# lightclock_0.net
KiCad netlist of a schematic drawn in EAGLE
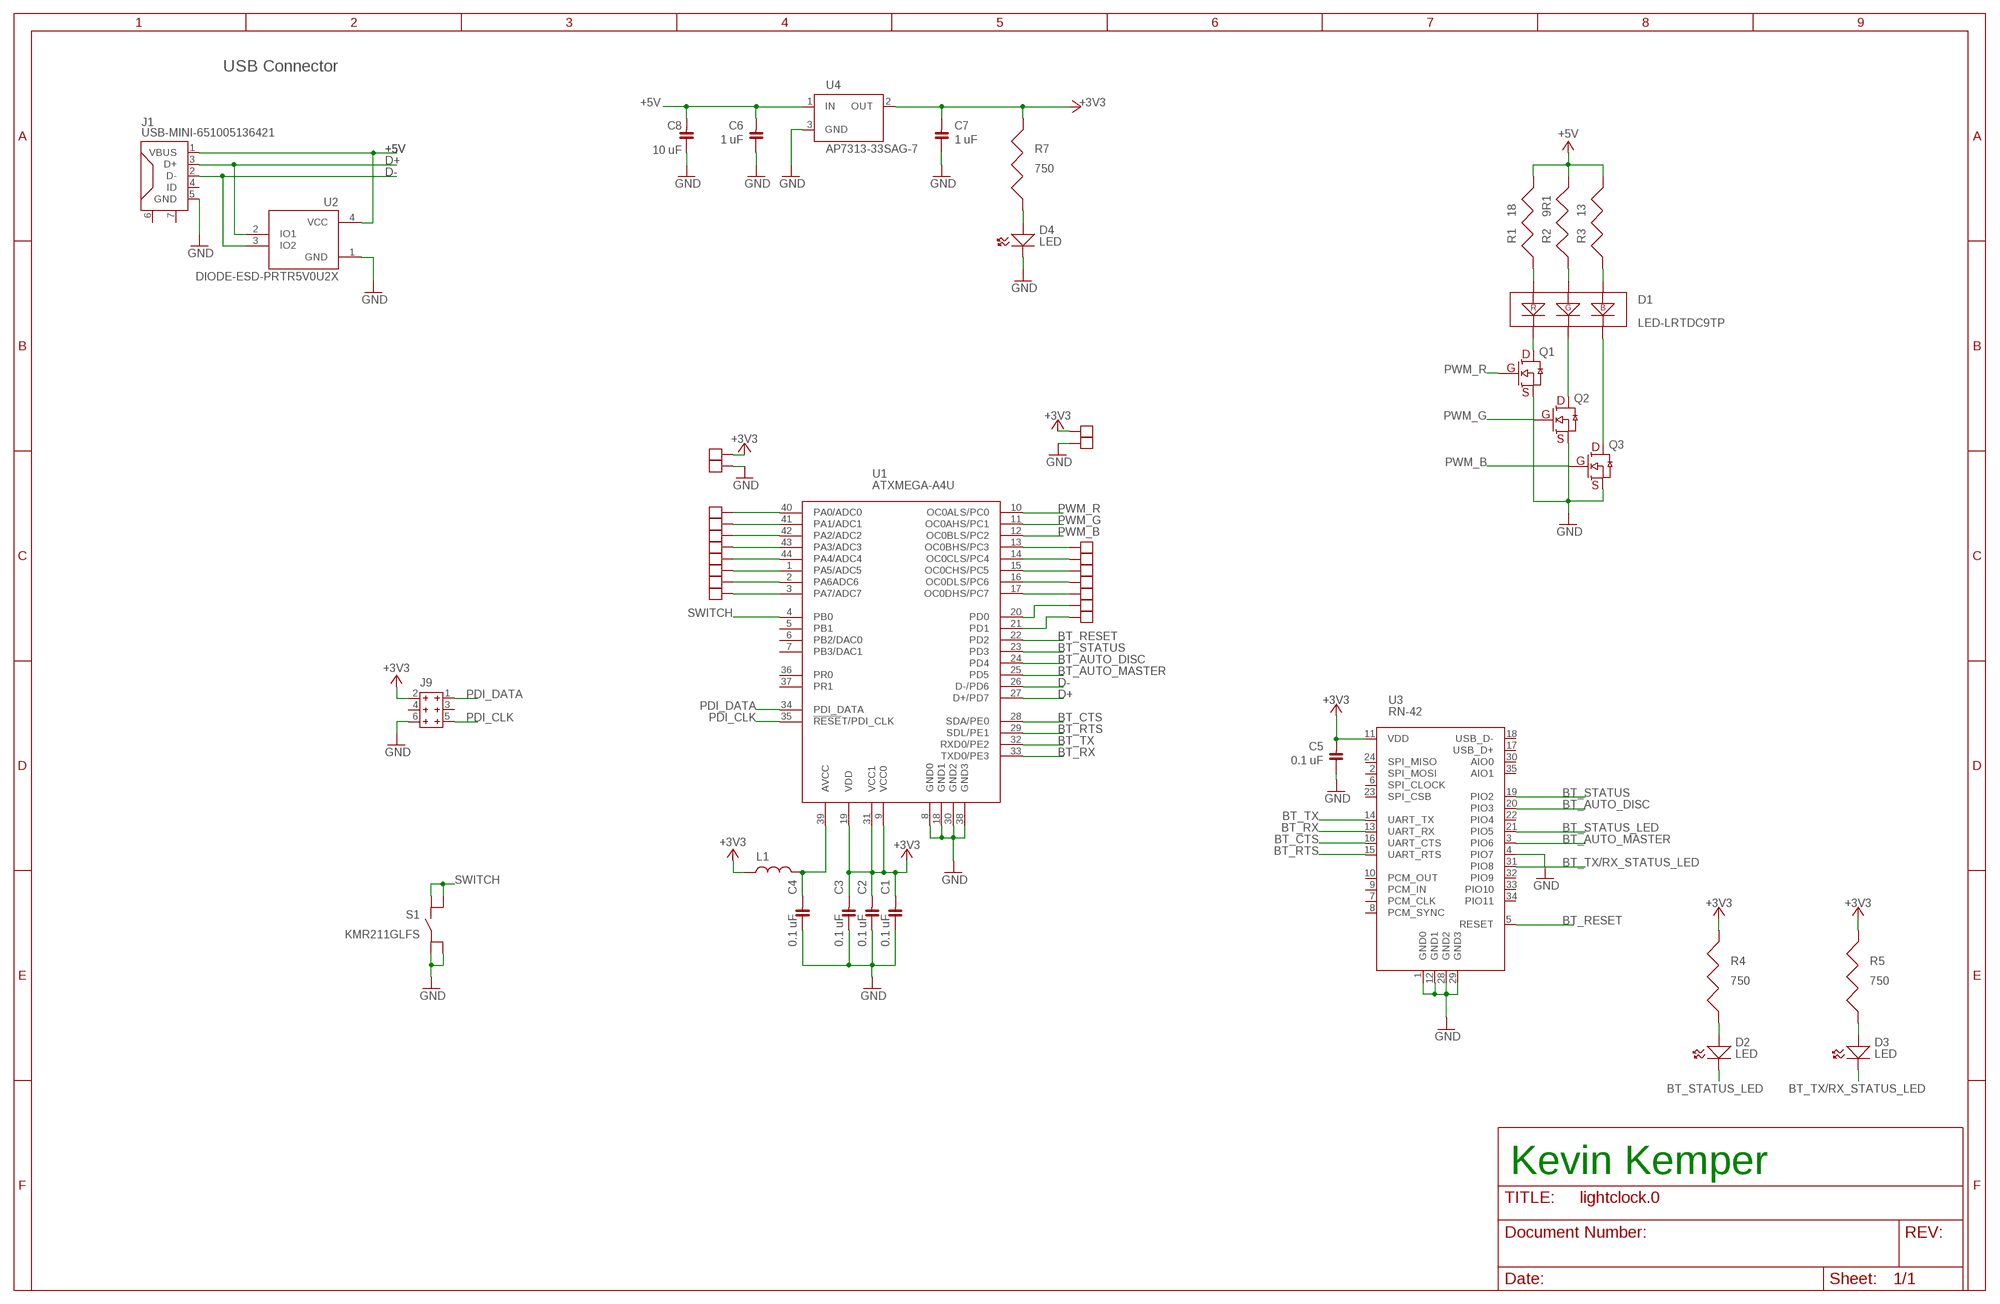
[diagram p0: schematic, sheet 1]

(export (version "E")
  (design (tool "Eeschema 10.0.6"))
  (components
    (comp (ref "C1")
      (value "0.1 uF")
      (footprint "eagle-import:0603")
      (libsource (lib "eagle-import") (part "CAP-0603"))
    )
    (comp (ref "C2")
      (value "0.1 uF")
      (footprint "eagle-import:0603")
      (libsource (lib "eagle-import") (part "CAP-0603"))
    )
    (comp (ref "C3")
      (value "0.1 uF")
      (footprint "eagle-import:0603")
      (libsource (lib "eagle-import") (part "CAP-0603"))
    )
    (comp (ref "C4")
      (value "0.1 uF")
      (footprint "eagle-import:0603")
      (libsource (lib "eagle-import") (part "CAP-0603"))
    )
    (comp (ref "C5")
      (value "0.1 uF")
      (footprint "eagle-import:0603")
      (libsource (lib "eagle-import") (part "CAP-0603"))
    )
    (comp (ref "C6")
      (value "1 uF")
      (footprint "eagle-import:0603")
      (libsource (lib "eagle-import") (part "CAP-0603"))
    )
    (comp (ref "C7")
      (value "1 uF")
      (footprint "eagle-import:0603")
      (libsource (lib "eagle-import") (part "CAP-0603"))
    )
    (comp (ref "C8")
      (value "10 uF")
      (footprint "eagle-import:0805")
      (libsource (lib "eagle-import") (part "CAP-0805"))
    )
    (comp (ref "D1")
      (value "LED-LRTDC9TP")
      (footprint "eagle-import:LRTDC9TP-EAFB-GHQN")
      (libsource (lib "eagle-import") (part "LED-LRTDC9TP"))
    )
    (comp (ref "D2")
      (value "LED")
      (footprint "eagle-import:0603-POL")
      (libsource (lib "eagle-import") (part "LED"))
    )
    (comp (ref "D3")
      (value "LED")
      (footprint "eagle-import:0603-POL")
      (libsource (lib "eagle-import") (part "LED"))
    )
    (comp (ref "D4")
      (value "LED")
      (footprint "eagle-import:0603-POL")
      (libsource (lib "eagle-import") (part "LED"))
    )
    (comp (ref "J1")
      (value "USB-MINI-651005136421")
      (footprint "eagle-import:651005136421")
      (libsource (lib "eagle-import") (part "USB-MINI-651005136421"))
    )
    (comp (ref "J2")
      (value "TESTPAD")
      (footprint "eagle-import:HEADER-1X1")
      (libsource (lib "eagle-import") (part "TESTPAD"))
    )
    (comp (ref "J3")
      (value "TESTPAD")
      (footprint "eagle-import:HEADER-1X1")
      (libsource (lib "eagle-import") (part "TESTPAD"))
    )
    (comp (ref "J4")
      (value "TESTPAD")
      (footprint "eagle-import:HEADER-1X1")
      (libsource (lib "eagle-import") (part "TESTPAD"))
    )
    (comp (ref "J5")
      (value "TESTPAD")
      (footprint "eagle-import:HEADER-1X1")
      (libsource (lib "eagle-import") (part "TESTPAD"))
    )
    (comp (ref "J6")
      (value "TESTPAD")
      (footprint "eagle-import:HEADER-1X1")
      (libsource (lib "eagle-import") (part "TESTPAD"))
    )
    (comp (ref "J7")
      (value "TESTPAD")
      (footprint "eagle-import:HEADER-1X1")
      (libsource (lib "eagle-import") (part "TESTPAD"))
    )
    (comp (ref "J8")
      (value "TESTPAD")
      (footprint "eagle-import:HEADER-1X1")
      (libsource (lib "eagle-import") (part "TESTPAD"))
    )
    (comp (ref "J9")
      (value "HEADER-2X6")
      (footprint "eagle-import:HEADER-2X6")
      (libsource (lib "eagle-import") (part "HEADER-2X6"))
    )
    (comp (ref "J10")
      (value "TESTPAD")
      (footprint "eagle-import:HEADER-1X1")
      (libsource (lib "eagle-import") (part "TESTPAD"))
    )
    (comp (ref "J11")
      (value "TESTPAD")
      (footprint "eagle-import:HEADER-1X1")
      (libsource (lib "eagle-import") (part "TESTPAD"))
    )
    (comp (ref "J12")
      (value "TESTPAD")
      (footprint "eagle-import:HEADER-1X1")
      (libsource (lib "eagle-import") (part "TESTPAD"))
    )
    (comp (ref "J13")
      (value "TESTPAD")
      (footprint "eagle-import:HEADER-1X1")
      (libsource (lib "eagle-import") (part "TESTPAD"))
    )
    (comp (ref "J14")
      (value "TESTPAD")
      (footprint "eagle-import:HEADER-1X1")
      (libsource (lib "eagle-import") (part "TESTPAD"))
    )
    (comp (ref "J15")
      (value "TESTPAD")
      (footprint "eagle-import:HEADER-1X1")
      (libsource (lib "eagle-import") (part "TESTPAD"))
    )
    (comp (ref "J16")
      (value "TESTPAD")
      (footprint "eagle-import:HEADER-1X1")
      (libsource (lib "eagle-import") (part "TESTPAD"))
    )
    (comp (ref "J17")
      (value "TESTPAD")
      (footprint "eagle-import:HEADER-1X1")
      (libsource (lib "eagle-import") (part "TESTPAD"))
    )
    (comp (ref "J18")
      (value "TESTPAD")
      (footprint "eagle-import:HEADER-1X1")
      (libsource (lib "eagle-import") (part "TESTPAD"))
    )
    (comp (ref "J19")
      (value "TESTPAD")
      (footprint "eagle-import:HEADER-1X1")
      (libsource (lib "eagle-import") (part "TESTPAD"))
    )
    (comp (ref "J20")
      (value "TESTPAD")
      (footprint "eagle-import:HEADER-1X1")
      (libsource (lib "eagle-import") (part "TESTPAD"))
    )
    (comp (ref "J21")
      (value "TESTPAD")
      (footprint "eagle-import:HEADER-1X1")
      (libsource (lib "eagle-import") (part "TESTPAD"))
    )
    (comp (ref "L1")
      (value "IND-0603")
      (footprint "eagle-import:0603")
      (libsource (lib "eagle-import") (part "IND-0603"))
    )
    (comp (ref "Q1")
      (value "BSS138")
      (footprint "eagle-import:SOT-23")
      (libsource (lib "eagle-import") (part "BSS138"))
    )
    (comp (ref "Q2")
      (value "BSS138")
      (footprint "eagle-import:SOT-23")
      (libsource (lib "eagle-import") (part "BSS138"))
    )
    (comp (ref "Q3")
      (value "BSS138")
      (footprint "eagle-import:SOT-23")
      (libsource (lib "eagle-import") (part "BSS138"))
    )
    (comp (ref "R1")
      (value "18")
      (footprint "eagle-import:2010")
      (libsource (lib "eagle-import") (part "RES2010"))
    )
    (comp (ref "R2")
      (value "9R1")
      (footprint "eagle-import:2010")
      (libsource (lib "eagle-import") (part "RES2010"))
    )
    (comp (ref "R3")
      (value "13")
      (footprint "eagle-import:2010")
      (libsource (lib "eagle-import") (part "RES2010"))
    )
    (comp (ref "R4")
      (value "750")
      (footprint "eagle-import:0603")
      (libsource (lib "eagle-import") (part "RES-0603"))
    )
    (comp (ref "R5")
      (value "750")
      (footprint "eagle-import:0603")
      (libsource (lib "eagle-import") (part "RES-0603"))
    )
    (comp (ref "R7")
      (value "750")
      (footprint "eagle-import:0603")
      (libsource (lib "eagle-import") (part "RES-0603"))
    )
    (comp (ref "S1")
      (value "KMR211GLFS")
      (footprint "eagle-import:KMR211GLFS")
      (libsource (lib "eagle-import") (part "KMR211GLFS"))
    )
    (comp (ref "U1")
      (value "ATXMEGA-A4U")
      (footprint "eagle-import:ATXMEGA16A4U-AUR")
      (libsource (lib "eagle-import") (part "ATXMEGA-A4U"))
    )
    (comp (ref "U2")
      (value "DIODE-ESD-PRTR5V0U2X")
      (footprint "eagle-import:PRTR5V0U2X")
      (libsource (lib "eagle-import") (part "DIODE-ESD-PRTR5V0U2X"))
    )
    (comp (ref "U3")
      (value "RN-42")
      (footprint "eagle-import:RN-42")
      (libsource (lib "eagle-import") (part "RN-42"))
    )
    (comp (ref "U4")
      (value "AP7313-33SAG-7")
      (footprint "eagle-import:AP7313-33SAG-7")
      (libsource (lib "eagle-import") (part "AP7313-33SAG-7"))
    )
  )
  (nets
    (net (code "1") (name "+3V3") (class "Default")
      (node (ref "C1") (pin "1") (pinfunction "1_1") (pintype "bidirectional"))
      (node (ref "C2") (pin "1") (pinfunction "1_1") (pintype "bidirectional"))
      (node (ref "C3") (pin "1") (pinfunction "1_1") (pintype "bidirectional"))
      (node (ref "C5") (pin "1") (pinfunction "1_1") (pintype "bidirectional"))
      (node (ref "C7") (pin "1") (pinfunction "1_1") (pintype "bidirectional"))
      (node (ref "J18") (pin "1") (pinfunction "P$1_1") (pintype "bidirectional"))
      (node (ref "J20") (pin "1") (pinfunction "P$1_1") (pintype "bidirectional"))
      (node (ref "J9") (pin "2") (pinfunction "2_2") (pintype "bidirectional"))
      (node (ref "L1") (pin "1") (pinfunction "P$1_1") (pintype "bidirectional"))
      (node (ref "R4") (pin "2") (pinfunction "P$2_2") (pintype "bidirectional"))
      (node (ref "R5") (pin "2") (pinfunction "P$2_2") (pintype "bidirectional"))
      (node (ref "R7") (pin "2") (pinfunction "P$2_2") (pintype "bidirectional"))
      (node (ref "U1") (pin "19") (pinfunction "VDD_19") (pintype "bidirectional"))
      (node (ref "U1") (pin "31") (pinfunction "VCC1_31") (pintype "bidirectional"))
      (node (ref "U1") (pin "9") (pinfunction "VCC0_9") (pintype "bidirectional"))
      (node (ref "U3") (pin "11") (pinfunction "VDD_11") (pintype "bidirectional"))
      (node (ref "U4") (pin "2") (pinfunction "OUT_2") (pintype "bidirectional"))
    )
    (net (code "2") (name "+5V") (class "Default")
      (node (ref "C6") (pin "1") (pinfunction "1_1") (pintype "bidirectional"))
      (node (ref "C8") (pin "1") (pinfunction "1_1") (pintype "bidirectional"))
      (node (ref "J1") (pin "1") (pinfunction "VBUS_1") (pintype "bidirectional"))
      (node (ref "R1") (pin "2") (pinfunction "P$2_2") (pintype "bidirectional"))
      (node (ref "R2") (pin "2") (pinfunction "P$2_2") (pintype "bidirectional"))
      (node (ref "R3") (pin "2") (pinfunction "P$2_2") (pintype "bidirectional"))
      (node (ref "U2") (pin "4") (pinfunction "VCC_4") (pintype "bidirectional"))
      (node (ref "U4") (pin "1") (pinfunction "IN_1") (pintype "bidirectional"))
    )
    (net (code "3") (name "/BT_AUTO_DISC") (class "Default")
      (node (ref "U1") (pin "24") (pinfunction "PD4_24") (pintype "bidirectional"))
      (node (ref "U3") (pin "20") (pinfunction "PIO3_20") (pintype "bidirectional"))
    )
    (net (code "4") (name "/BT_AUTO_MASTER") (class "Default")
      (node (ref "U1") (pin "25") (pinfunction "PD5_25") (pintype "bidirectional"))
      (node (ref "U3") (pin "3") (pinfunction "PIO6_3") (pintype "bidirectional"))
    )
    (net (code "5") (name "/BT_CTS") (class "Default")
      (node (ref "U1") (pin "28") (pinfunction "SDA/PE0_28") (pintype "bidirectional"))
      (node (ref "U3") (pin "16") (pinfunction "UART_CTS_16") (pintype "bidirectional"))
    )
    (net (code "6") (name "/BT_RESET") (class "Default")
      (node (ref "U1") (pin "22") (pinfunction "PD2_22") (pintype "bidirectional"))
      (node (ref "U3") (pin "5") (pinfunction "RESET_5") (pintype "bidirectional"))
    )
    (net (code "7") (name "/BT_RTS") (class "Default")
      (node (ref "U1") (pin "29") (pinfunction "SDL/PE1_29") (pintype "bidirectional"))
      (node (ref "U3") (pin "15") (pinfunction "UART_RTS_15") (pintype "bidirectional"))
    )
    (net (code "8") (name "/BT_RX") (class "Default")
      (node (ref "U1") (pin "33") (pinfunction "TXD0/PE3_33") (pintype "bidirectional"))
      (node (ref "U3") (pin "13") (pinfunction "UART_RX_13") (pintype "bidirectional"))
    )
    (net (code "9") (name "/BT_STATUS") (class "Default")
      (node (ref "U1") (pin "23") (pinfunction "PD3_23") (pintype "bidirectional"))
      (node (ref "U3") (pin "19") (pinfunction "PIO2_19") (pintype "bidirectional"))
    )
    (net (code "10") (name "/BT_STATUS_LED") (class "Default")
      (node (ref "D2") (pin "2") (pinfunction "2_2") (pintype "bidirectional"))
      (node (ref "U3") (pin "21") (pinfunction "PIO5_21") (pintype "bidirectional"))
    )
    (net (code "11") (name "/BT_TX") (class "Default")
      (node (ref "U1") (pin "32") (pinfunction "RXD0/PE2_32") (pintype "bidirectional"))
      (node (ref "U3") (pin "14") (pinfunction "UART_TX_14") (pintype "bidirectional"))
    )
    (net (code "12") (name "/BT_TX{slash}RX_STATUS_LED") (class "Default")
      (node (ref "D3") (pin "2") (pinfunction "2_2") (pintype "bidirectional"))
      (node (ref "U3") (pin "31") (pinfunction "PIO8_31") (pintype "bidirectional"))
    )
    (net (code "13") (name "/D+") (class "Default")
      (node (ref "J1") (pin "3") (pinfunction "D+_3") (pintype "bidirectional"))
      (node (ref "U1") (pin "27") (pinfunction "D+/PD7_27") (pintype "bidirectional"))
      (node (ref "U2") (pin "2") (pinfunction "IO1_2") (pintype "bidirectional"))
    )
    (net (code "14") (name "/D-") (class "Default")
      (node (ref "J1") (pin "2") (pinfunction "D-_2") (pintype "bidirectional"))
      (node (ref "U1") (pin "26") (pinfunction "D-/PD6_26") (pintype "bidirectional"))
      (node (ref "U2") (pin "3") (pinfunction "IO2_3") (pintype "bidirectional"))
    )
    (net (code "15") (name "/PDI_CLK") (class "Default")
      (node (ref "J9") (pin "5") (pinfunction "5_5") (pintype "bidirectional"))
      (node (ref "U1") (pin "35") (pinfunction "~{RESE}T/PDI_CLK_35") (pintype "bidirectional"))
    )
    (net (code "16") (name "/PDI_DATA") (class "Default")
      (node (ref "J9") (pin "1") (pinfunction "1_1") (pintype "bidirectional"))
      (node (ref "U1") (pin "34") (pinfunction "PDI_DATA_34") (pintype "bidirectional"))
    )
    (net (code "17") (name "/PWM_B") (class "Default")
      (node (ref "Q3") (pin "1") (pinfunction "G_1") (pintype "bidirectional"))
      (node (ref "U1") (pin "12") (pinfunction "OC0BLS/PC2_12") (pintype "bidirectional"))
    )
    (net (code "18") (name "/PWM_G") (class "Default")
      (node (ref "Q2") (pin "1") (pinfunction "G_1") (pintype "bidirectional"))
      (node (ref "U1") (pin "11") (pinfunction "OC0AHS/PC1_11") (pintype "bidirectional"))
    )
    (net (code "19") (name "/PWM_R") (class "Default")
      (node (ref "Q1") (pin "1") (pinfunction "G_1") (pintype "bidirectional"))
      (node (ref "U1") (pin "10") (pinfunction "OC0ALS/PC0_10") (pintype "bidirectional"))
    )
    (net (code "20") (name "/SWITCH") (class "Default")
      (node (ref "S1") (pin "3") (pinfunction "3_3") (pintype "bidirectional"))
      (node (ref "S1") (pin "4") (pinfunction "4_4") (pintype "bidirectional"))
      (node (ref "U1") (pin "4") (pinfunction "PB0_4") (pintype "bidirectional"))
    )
    (net (code "21") (name "GND") (class "Default")
      (node (ref "C1") (pin "2") (pinfunction "2_2") (pintype "bidirectional"))
      (node (ref "C2") (pin "2") (pinfunction "2_2") (pintype "bidirectional"))
      (node (ref "C3") (pin "2") (pinfunction "2_2") (pintype "bidirectional"))
      (node (ref "C4") (pin "2") (pinfunction "2_2") (pintype "bidirectional"))
      (node (ref "C5") (pin "2") (pinfunction "2_2") (pintype "bidirectional"))
      (node (ref "C6") (pin "2") (pinfunction "2_2") (pintype "bidirectional"))
      (node (ref "C7") (pin "2") (pinfunction "2_2") (pintype "bidirectional"))
      (node (ref "C8") (pin "2") (pinfunction "2_2") (pintype "bidirectional"))
      (node (ref "D4") (pin "2") (pinfunction "2_2") (pintype "bidirectional"))
      (node (ref "J1") (pin "5") (pinfunction "GND_5") (pintype "bidirectional"))
      (node (ref "J19") (pin "1") (pinfunction "P$1_1") (pintype "bidirectional"))
      (node (ref "J21") (pin "1") (pinfunction "P$1_1") (pintype "bidirectional"))
      (node (ref "J9") (pin "6") (pinfunction "6_6") (pintype "bidirectional"))
      (node (ref "Q1") (pin "2") (pinfunction "S_2") (pintype "bidirectional"))
      (node (ref "Q2") (pin "2") (pinfunction "S_2") (pintype "bidirectional"))
      (node (ref "Q3") (pin "2") (pinfunction "S_2") (pintype "bidirectional"))
      (node (ref "S1") (pin "1") (pinfunction "1_1") (pintype "bidirectional"))
      (node (ref "S1") (pin "2") (pinfunction "2_2") (pintype "bidirectional"))
      (node (ref "U1") (pin "18") (pinfunction "GND1_18") (pintype "bidirectional"))
      (node (ref "U1") (pin "30") (pinfunction "GND2_30") (pintype "bidirectional"))
      (node (ref "U1") (pin "38") (pinfunction "GND3_38") (pintype "bidirectional"))
      (node (ref "U1") (pin "8") (pinfunction "GND0_8") (pintype "bidirectional"))
      (node (ref "U2") (pin "1") (pinfunction "GND_1") (pintype "bidirectional"))
      (node (ref "U3") (pin "1") (pinfunction "GND0_1") (pintype "bidirectional"))
      (node (ref "U3") (pin "12") (pinfunction "GND1_12") (pintype "bidirectional"))
      (node (ref "U3") (pin "28") (pinfunction "GND2_28") (pintype "bidirectional"))
      (node (ref "U3") (pin "29") (pinfunction "GND3_29") (pintype "bidirectional"))
      (node (ref "U3") (pin "4") (pinfunction "PIO7_4") (pintype "bidirectional"))
      (node (ref "U4") (pin "3") (pinfunction "GND_3") (pintype "bidirectional"))
    )
    (net (code "22") (name "Net-(J2-P$1)") (class "Default")
      (node (ref "J2") (pin "1") (pinfunction "P$1_1") (pintype "bidirectional"))
      (node (ref "U1") (pin "13") (pinfunction "OC0BHS/PC3_13") (pintype "bidirectional"))
    )
    (net (code "23") (name "Net-(J3-P$1)") (class "Default")
      (node (ref "J3") (pin "1") (pinfunction "P$1_1") (pintype "bidirectional"))
      (node (ref "U1") (pin "14") (pinfunction "OC0CLS/PC4_14") (pintype "bidirectional"))
    )
    (net (code "24") (name "Net-(J4-P$1)") (class "Default")
      (node (ref "J4") (pin "1") (pinfunction "P$1_1") (pintype "bidirectional"))
      (node (ref "U1") (pin "15") (pinfunction "OC0CHS/PC5_15") (pintype "bidirectional"))
    )
    (net (code "25") (name "Net-(J5-P$1)") (class "Default")
      (node (ref "J5") (pin "1") (pinfunction "P$1_1") (pintype "bidirectional"))
      (node (ref "U1") (pin "16") (pinfunction "OC0DLS/PC6_16") (pintype "bidirectional"))
    )
    (net (code "26") (name "Net-(J6-P$1)") (class "Default")
      (node (ref "J6") (pin "1") (pinfunction "P$1_1") (pintype "bidirectional"))
      (node (ref "U1") (pin "17") (pinfunction "OC0DHS/PC7_17") (pintype "bidirectional"))
    )
    (net (code "27") (name "Net-(J7-P$1)") (class "Default")
      (node (ref "J7") (pin "1") (pinfunction "P$1_1") (pintype "bidirectional"))
      (node (ref "U1") (pin "20") (pinfunction "PD0_20") (pintype "bidirectional"))
    )
    (net (code "28") (name "Net-(J8-P$1)") (class "Default")
      (node (ref "J8") (pin "1") (pinfunction "P$1_1") (pintype "bidirectional"))
      (node (ref "U1") (pin "21") (pinfunction "PD1_21") (pintype "bidirectional"))
    )
    (net (code "29") (name "Net-(J10-P$1)") (class "Default")
      (node (ref "J10") (pin "1") (pinfunction "P$1_1") (pintype "bidirectional"))
      (node (ref "U1") (pin "40") (pinfunction "PA0/ADC0_40") (pintype "bidirectional"))
    )
    (net (code "30") (name "Net-(J11-P$1)") (class "Default")
      (node (ref "J11") (pin "1") (pinfunction "P$1_1") (pintype "bidirectional"))
      (node (ref "U1") (pin "41") (pinfunction "PA1/ADC1_41") (pintype "bidirectional"))
    )
    (net (code "31") (name "Net-(J12-P$1)") (class "Default")
      (node (ref "J12") (pin "1") (pinfunction "P$1_1") (pintype "bidirectional"))
      (node (ref "U1") (pin "42") (pinfunction "PA2/ADC2_42") (pintype "bidirectional"))
    )
    (net (code "32") (name "Net-(J13-P$1)") (class "Default")
      (node (ref "J13") (pin "1") (pinfunction "P$1_1") (pintype "bidirectional"))
      (node (ref "U1") (pin "43") (pinfunction "PA3/ADC3_43") (pintype "bidirectional"))
    )
    (net (code "33") (name "Net-(J14-P$1)") (class "Default")
      (node (ref "J14") (pin "1") (pinfunction "P$1_1") (pintype "bidirectional"))
      (node (ref "U1") (pin "44") (pinfunction "PA4/ADC4_44") (pintype "bidirectional"))
    )
    (net (code "34") (name "Net-(J15-P$1)") (class "Default")
      (node (ref "J15") (pin "1") (pinfunction "P$1_1") (pintype "bidirectional"))
      (node (ref "U1") (pin "1") (pinfunction "PA5/ADC5_1") (pintype "bidirectional"))
    )
    (net (code "35") (name "Net-(J16-P$1)") (class "Default")
      (node (ref "J16") (pin "1") (pinfunction "P$1_1") (pintype "bidirectional"))
      (node (ref "U1") (pin "2") (pinfunction "PA6ADC6_2") (pintype "bidirectional"))
    )
    (net (code "36") (name "Net-(J17-P$1)") (class "Default")
      (node (ref "J17") (pin "1") (pinfunction "P$1_1") (pintype "bidirectional"))
      (node (ref "U1") (pin "3") (pinfunction "PA7/ADC7_3") (pintype "bidirectional"))
    )
    (net (code "37") (name "Net-(L1-P$2)") (class "Default")
      (node (ref "C4") (pin "1") (pinfunction "1_1") (pintype "bidirectional"))
      (node (ref "L1") (pin "2") (pinfunction "P$2_2") (pintype "bidirectional"))
      (node (ref "U1") (pin "39") (pinfunction "AVCC_39") (pintype "bidirectional"))
    )
    (net (code "38") (name "Net-(Q1-D)") (class "Default")
      (node (ref "D1") (pin "C1") (pinfunction "C1_C1") (pintype "bidirectional"))
      (node (ref "Q1") (pin "3") (pinfunction "D_3") (pintype "bidirectional"))
    )
    (net (code "39") (name "Net-(Q2-D)") (class "Default")
      (node (ref "D1") (pin "C2") (pinfunction "C2_C2") (pintype "bidirectional"))
      (node (ref "Q2") (pin "3") (pinfunction "D_3") (pintype "bidirectional"))
    )
    (net (code "40") (name "Net-(Q3-D)") (class "Default")
      (node (ref "D1") (pin "C3") (pinfunction "C3_C3") (pintype "bidirectional"))
      (node (ref "Q3") (pin "3") (pinfunction "D_3") (pintype "bidirectional"))
    )
    (net (code "41") (name "Net-(R1-P$1)") (class "Default")
      (node (ref "D1") (pin "A1") (pinfunction "A1_A1") (pintype "bidirectional"))
      (node (ref "R1") (pin "1") (pinfunction "P$1_1") (pintype "bidirectional"))
    )
    (net (code "42") (name "Net-(R2-P$1)") (class "Default")
      (node (ref "D1") (pin "A2") (pinfunction "A2_A2") (pintype "bidirectional"))
      (node (ref "R2") (pin "1") (pinfunction "P$1_1") (pintype "bidirectional"))
    )
    (net (code "43") (name "Net-(R3-P$1)") (class "Default")
      (node (ref "D1") (pin "A3") (pinfunction "A3_A3") (pintype "bidirectional"))
      (node (ref "R3") (pin "1") (pinfunction "P$1_1") (pintype "bidirectional"))
    )
    (net (code "44") (name "Net-(R4-P$1)") (class "Default")
      (node (ref "D2") (pin "1") (pinfunction "1_1") (pintype "bidirectional"))
      (node (ref "R4") (pin "1") (pinfunction "P$1_1") (pintype "bidirectional"))
    )
    (net (code "45") (name "Net-(R5-P$1)") (class "Default")
      (node (ref "D3") (pin "1") (pinfunction "1_1") (pintype "bidirectional"))
      (node (ref "R5") (pin "1") (pinfunction "P$1_1") (pintype "bidirectional"))
    )
    (net (code "46") (name "Net-(R7-P$1)") (class "Default")
      (node (ref "D4") (pin "1") (pinfunction "1_1") (pintype "bidirectional"))
      (node (ref "R7") (pin "1") (pinfunction "P$1_1") (pintype "bidirectional"))
    )
    (net (code "47") (name "unconnected-(J1-ID-Pad4)") (class "Default")
      (node (ref "J1") (pin "4") (pinfunction "ID_4") (pintype "bidirectional"))
    )
    (net (code "48") (name "unconnected-(J1-SHEILD1-Pad6)") (class "Default")
      (node (ref "J1") (pin "6") (pinfunction "SHEILD1_6") (pintype "bidirectional"))
    )
    (net (code "49") (name "unconnected-(J1-SHEILD2-Pad7)") (class "Default")
      (node (ref "J1") (pin "7") (pinfunction "SHEILD2_7") (pintype "bidirectional"))
    )
    (net (code "50") (name "unconnected-(J9-Pad3)") (class "Default")
      (node (ref "J9") (pin "3") (pinfunction "3_3") (pintype "bidirectional"))
    )
    (net (code "51") (name "unconnected-(J9-Pad4)") (class "Default")
      (node (ref "J9") (pin "4") (pinfunction "4_4") (pintype "bidirectional"))
    )
    (net (code "52") (name "unconnected-(U1-PB1-Pad5)") (class "Default")
      (node (ref "U1") (pin "5") (pinfunction "PB1_5") (pintype "bidirectional"))
    )
    (net (code "53") (name "unconnected-(U1-PB2{slash}DAC0-Pad6)") (class "Default")
      (node (ref "U1") (pin "6") (pinfunction "PB2/DAC0_6") (pintype "bidirectional"))
    )
    (net (code "54") (name "unconnected-(U1-PB3{slash}DAC1-Pad7)") (class "Default")
      (node (ref "U1") (pin "7") (pinfunction "PB3/DAC1_7") (pintype "bidirectional"))
    )
    (net (code "55") (name "unconnected-(U1-PR0-Pad36)") (class "Default")
      (node (ref "U1") (pin "36") (pinfunction "PR0_36") (pintype "bidirectional"))
    )
    (net (code "56") (name "unconnected-(U1-PR1-Pad37)") (class "Default")
      (node (ref "U1") (pin "37") (pinfunction "PR1_37") (pintype "bidirectional"))
    )
    (net (code "57") (name "unconnected-(U3-AIO0-Pad30)") (class "Default")
      (node (ref "U3") (pin "30") (pinfunction "AIO0_30") (pintype "bidirectional"))
    )
    (net (code "58") (name "unconnected-(U3-AIO1-Pad35)") (class "Default")
      (node (ref "U3") (pin "35") (pinfunction "AIO1_35") (pintype "bidirectional"))
    )
    (net (code "59") (name "unconnected-(U3-PCM_CLK-Pad7)") (class "Default")
      (node (ref "U3") (pin "7") (pinfunction "PCM_CLK_7") (pintype "bidirectional"))
    )
    (net (code "60") (name "unconnected-(U3-PCM_IN-Pad9)") (class "Default")
      (node (ref "U3") (pin "9") (pinfunction "PCM_IN_9") (pintype "bidirectional"))
    )
    (net (code "61") (name "unconnected-(U3-PCM_OUT-Pad10)") (class "Default")
      (node (ref "U3") (pin "10") (pinfunction "PCM_OUT_10") (pintype "bidirectional"))
    )
    (net (code "62") (name "unconnected-(U3-PCM_SYNC-Pad8)") (class "Default")
      (node (ref "U3") (pin "8") (pinfunction "PCM_SYNC_8") (pintype "bidirectional"))
    )
    (net (code "63") (name "unconnected-(U3-PIO4-Pad22)") (class "Default")
      (node (ref "U3") (pin "22") (pinfunction "PIO4_22") (pintype "bidirectional"))
    )
    (net (code "64") (name "unconnected-(U3-PIO9-Pad32)") (class "Default")
      (node (ref "U3") (pin "32") (pinfunction "PIO9_32") (pintype "bidirectional"))
    )
    (net (code "65") (name "unconnected-(U3-PIO10-Pad33)") (class "Default")
      (node (ref "U3") (pin "33") (pinfunction "PIO10_33") (pintype "bidirectional"))
    )
    (net (code "66") (name "unconnected-(U3-PIO11-Pad34)") (class "Default")
      (node (ref "U3") (pin "34") (pinfunction "PIO11_34") (pintype "bidirectional"))
    )
    (net (code "67") (name "unconnected-(U3-SPI_CLOCK-Pad6)") (class "Default")
      (node (ref "U3") (pin "6") (pinfunction "SPI_CLOCK_6") (pintype "bidirectional"))
    )
    (net (code "68") (name "unconnected-(U3-SPI_CSB-Pad23)") (class "Default")
      (node (ref "U3") (pin "23") (pinfunction "SPI_CSB_23") (pintype "bidirectional"))
    )
    (net (code "69") (name "unconnected-(U3-SPI_MISO-Pad24)") (class "Default")
      (node (ref "U3") (pin "24") (pinfunction "SPI_MISO_24") (pintype "bidirectional"))
    )
    (net (code "70") (name "unconnected-(U3-SPI_MOSI-Pad2)") (class "Default")
      (node (ref "U3") (pin "2") (pinfunction "SPI_MOSI_2") (pintype "bidirectional"))
    )
    (net (code "71") (name "unconnected-(U3-USB_D+-Pad17)") (class "Default")
      (node (ref "U3") (pin "17") (pinfunction "USB_D+_17") (pintype "bidirectional"))
    )
    (net (code "72") (name "unconnected-(U3-USB_D--Pad18)") (class "Default")
      (node (ref "U3") (pin "18") (pinfunction "USB_D-_18") (pintype "bidirectional"))
    )
  )
)
